# SD_Card_and_Debug_Uart.net
KiCad netlist of a schematic drawn in Altium Designer
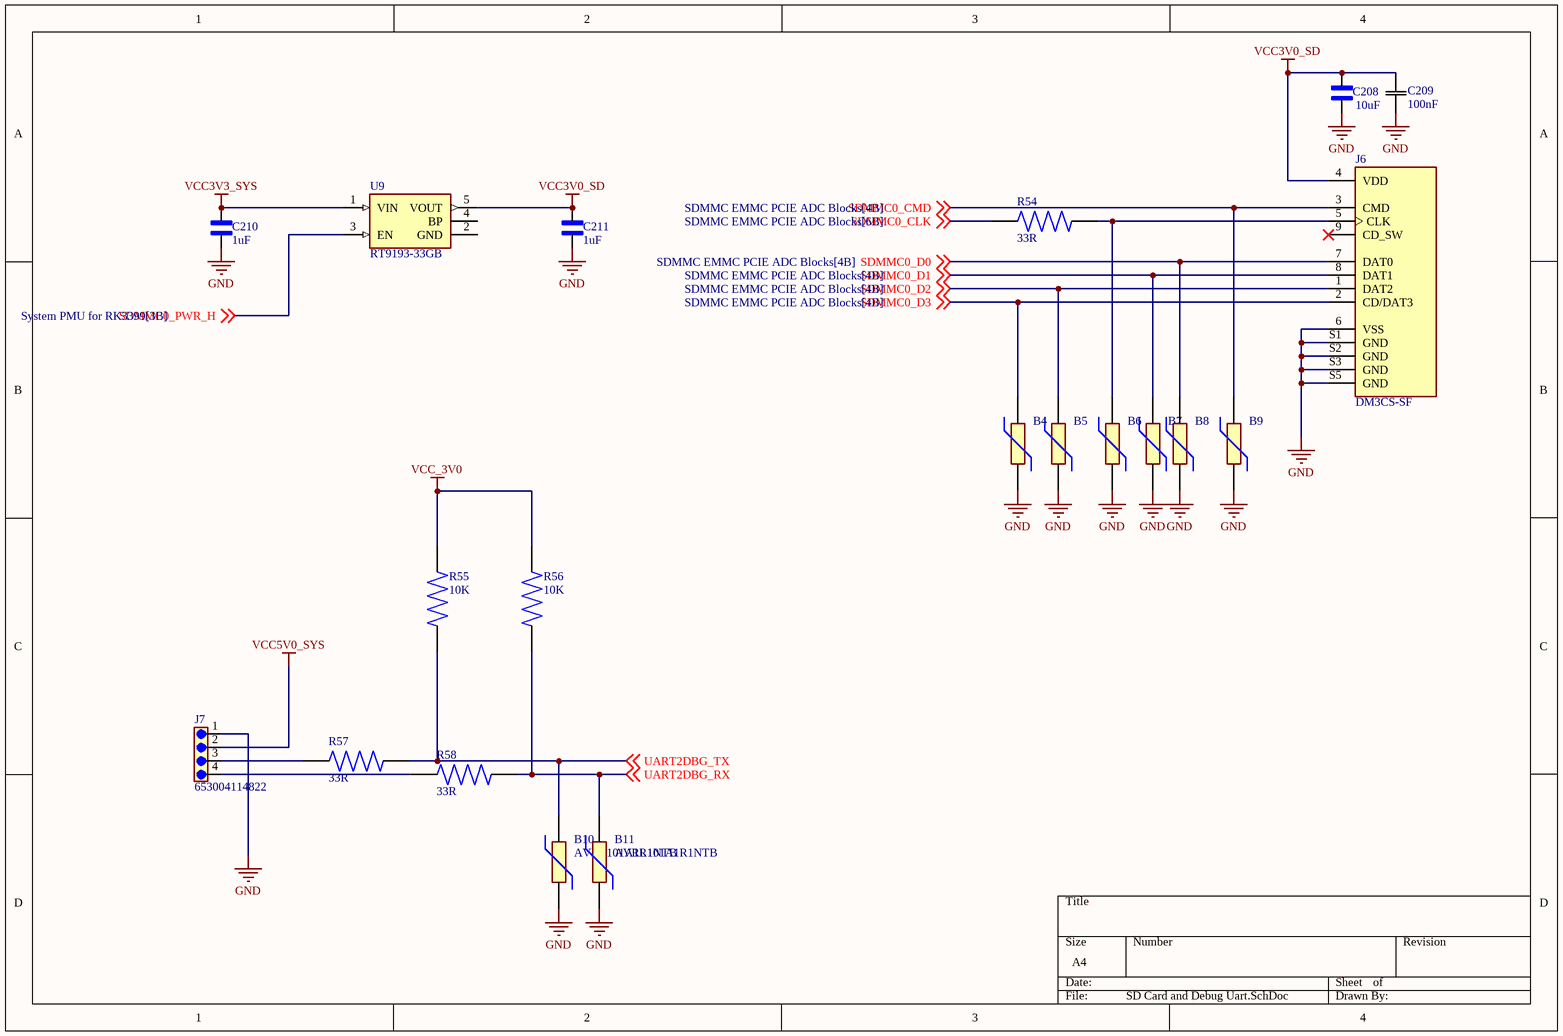
[diagram p0: SD Card and Debug Uart.SchDoc]

(export (version "E")
  (design (tool "Eeschema 10.0.6"))
  (components
    (comp (ref "B4")
      (value "~")
      (footprint "VARC1005X55N")
      (fields
        (field (name "MANUFACTURER_PART_NUMBER") "AVRL101A1R1NTB")
        (field (name "MOUSER PART NUMBER") "810-AVRL101A1R1NTB")
      )
      (libsource (lib "AVRL101A1R1NTB") (part "AVRL101A1R1NTB"))
    )
    (comp (ref "B5")
      (value "~")
      (footprint "VARC1005X55N")
      (fields
        (field (name "MANUFACTURER_PART_NUMBER") "AVRL101A1R1NTB")
        (field (name "MOUSER PART NUMBER") "810-AVRL101A1R1NTB")
      )
      (libsource (lib "AVRL101A1R1NTB") (part "AVRL101A1R1NTB"))
    )
    (comp (ref "B6")
      (value "~")
      (footprint "VARC1005X55N")
      (fields
        (field (name "MANUFACTURER_PART_NUMBER") "AVRL101A1R1NTB")
        (field (name "MOUSER PART NUMBER") "810-AVRL101A1R1NTB")
      )
      (libsource (lib "AVRL101A1R1NTB") (part "AVRL101A1R1NTB"))
    )
    (comp (ref "B7")
      (value "~")
      (footprint "VARC1005X55N")
      (fields
        (field (name "MANUFACTURER_PART_NUMBER") "AVRL101A1R1NTB")
        (field (name "MOUSER PART NUMBER") "810-AVRL101A1R1NTB")
      )
      (libsource (lib "AVRL101A1R1NTB") (part "AVRL101A1R1NTB"))
    )
    (comp (ref "B8")
      (value "~")
      (footprint "VARC1005X55N")
      (fields
        (field (name "MANUFACTURER_PART_NUMBER") "AVRL101A1R1NTB")
        (field (name "MOUSER PART NUMBER") "810-AVRL101A1R1NTB")
      )
      (libsource (lib "AVRL101A1R1NTB") (part "AVRL101A1R1NTB"))
    )
    (comp (ref "B9")
      (value "~")
      (footprint "VARC1005X55N")
      (fields
        (field (name "MANUFACTURER_PART_NUMBER") "AVRL101A1R1NTB")
        (field (name "MOUSER PART NUMBER") "810-AVRL101A1R1NTB")
      )
      (libsource (lib "AVRL101A1R1NTB") (part "AVRL101A1R1NTB"))
    )
    (comp (ref "B10")
      (value "AVRL101A1R1NTB")
      (footprint "VARC1005X55N")
      (fields (field (name "MOUSER PART NUMBER") "810-AVRL101A1R1NTB"))
      (libsource (lib "AVRL101A1R1NTB") (part "AVRL101A1R1NTB"))
    )
    (comp (ref "B11")
      (value "AVRL101A1R1NTB")
      (footprint "VARC1005X55N")
      (fields (field (name "MOUSER PART NUMBER") "810-AVRL101A1R1NTB"))
      (libsource (lib "AVRL101A1R1NTB") (part "AVRL101A1R1NTB"))
    )
    (comp (ref "C208")
      (value "10uF")
      (footprint "CAPC1005X70N")
      (description "10 ÂµF Â±20% 6.3V Ceramic Capacitor X5R 0402 (1005 Metric)")
      (fields (field (name "MF") "Samsung") (field (name "MP") "CL05A106MQ5NUNC"))
      (libsource (lib "CL05A106MQ5NUNC") (part "CL05A106MQ5NUNC"))
    )
    (comp (ref "C209")
      (value "100nF")
      (footprint "CAP_1005_TDK")
      (description "Description")
      (fields
        (field (name "MANUFACTURER_PART_NUMBER") "C1005X7R1H104M050BB")
        (field (name "COPYRIGHT") "Copyright (C) 2025 Ultra Librarian. All rights reserved.")
      )
      (libsource (lib "C1005X7R1H104M050BB") (part "C1005X7R1H104M050BB"))
    )
    (comp (ref "C210")
      (value "1uF")
      (footprint "CAPC1005X56N")
      (description "1 ÂµF Â±10% 10V Ceramic Capacitor X5R 0402 (1005 Metric)")
      (fields (field (name "MF") "AVX") (field (name "MP") "0402ZD105KAT4A"))
      (libsource (lib "0402ZD105KAT4A") (part "0402ZD105KAT4A"))
    )
    (comp (ref "C211")
      (value "1uF")
      (footprint "CAPC1005X56N")
      (description "1 ÂµF Â±10% 10V Ceramic Capacitor X5R 0402 (1005 Metric)")
      (fields (field (name "MF") "AVX") (field (name "MP") "0402ZD105KAT4A"))
      (libsource (lib "0402ZD105KAT4A") (part "0402ZD105KAT4A"))
    )
    (comp (ref "J6")
      (value "DM3CS-SF")
      (footprint "HRS_DM3CS-SF")
      (description "10 (8 + 2) Position Card Connector Secure Digital - microSDâ„¢ Surface Mount, Right Angle Gold")
      (fields (field (name "MF") "Hirose Electric Co Ltd"))
      (libsource (lib "DM3CS-SF") (part "DM3CS-SF"))
    )
    (comp (ref "J7")
      (value "653004114822")
      (footprint "653004114822")
      (description "CONN, HEADER, 4POS, 1ROW, 1.25MM ROHS COMPLIANT: YES")
      (fields (field (name "MF") "WÃ¼rth Elektronik"))
      (libsource (lib "653004114822") (part "653004114822"))
    )
    (comp (ref "R54")
      (value "33R")
      (footprint "RES_ERA6AHD330V")
      (fields (field (name "MP") "ERA6AHD330V"))
      (libsource (lib "ERA6AHD330V") (part "ERA6AHD330V"))
    )
    (comp (ref "R55")
      (value "10K")
      (footprint "RES_ERA3ARB103V")
      (fields (field (name "MP") "ERA3ARB103V"))
      (libsource (lib "ERA3ARB103V") (part "ERA3ARB103V"))
    )
    (comp (ref "R56")
      (value "10K")
      (footprint "RES_ERA3ARB103V")
      (fields (field (name "MP") "ERA3ARB103V"))
      (libsource (lib "ERA3ARB103V") (part "ERA3ARB103V"))
    )
    (comp (ref "R57")
      (value "33R")
      (footprint "RES_ERA6AHD330V")
      (fields (field (name "MP") "ERA6AHD330V"))
      (libsource (lib "ERA6AHD330V") (part "ERA6AHD330V"))
    )
    (comp (ref "R58")
      (value "33R")
      (footprint "RES_ERA6AHD330V")
      (fields (field (name "MP") "ERA6AHD330V"))
      (libsource (lib "ERA6AHD330V") (part "ERA6AHD330V"))
    )
    (comp (ref "U9")
      (value "RT9193-33GB")
      (footprint "SOT94P279X129-5N")
      (description "Linear Voltage Regulator IC Positive Fixed 1 Output 300mA TSOT-23-5")
      (fields (field (name "MF") "Richtek USA") (field (name "DIGI-KEY_PART_NUMBER") "1028-1014-2-ND"))
      (libsource (lib "RT9193-33GB") (part "RT9193-33GB"))
    )
  )
  (nets
    (net (code "1") (name "GND") (class "Default")
      (node (ref "B10") (pin "1") (pinfunction "1_1") (pintype "passive"))
      (node (ref "B11") (pin "1") (pinfunction "1_1") (pintype "passive"))
      (node (ref "B4") (pin "1") (pinfunction "1_1") (pintype "passive"))
      (node (ref "B5") (pin "1") (pinfunction "1_1") (pintype "passive"))
      (node (ref "B6") (pin "1") (pinfunction "1_1") (pintype "passive"))
      (node (ref "B7") (pin "1") (pinfunction "1_1") (pintype "passive"))
      (node (ref "B8") (pin "1") (pinfunction "1_1") (pintype "passive"))
      (node (ref "B9") (pin "1") (pinfunction "1_1") (pintype "passive"))
      (node (ref "C208") (pin "1") (pinfunction "1_1") (pintype "passive"))
      (node (ref "C209") (pin "1") (pinfunction "1_1") (pintype "passive"))
      (node (ref "C210") (pin "1") (pinfunction "1_1") (pintype "passive"))
      (node (ref "C211") (pin "1") (pinfunction "1_1") (pintype "passive"))
      (node (ref "J6") (pin "6") (pinfunction "VSS_6") (pintype "passive"))
      (node (ref "J6") (pin "S1") (pinfunction "GND_S1") (pintype "passive"))
      (node (ref "J6") (pin "S2") (pinfunction "GND_S2") (pintype "passive"))
      (node (ref "J6") (pin "S3") (pinfunction "GND_S3") (pintype "passive"))
      (node (ref "J6") (pin "S5") (pinfunction "GND_S5") (pintype "passive"))
      (node (ref "J7") (pin "1") (pinfunction "1_1") (pintype "passive"))
    )
    (net (code "2") (name "Net-(J6-CLK)") (class "Default")
      (node (ref "B6") (pin "2") (pinfunction "2_2") (pintype "passive"))
      (node (ref "J6") (pin "5") (pinfunction "CLK_5") (pintype "passive"))
      (node (ref "R54") (pin "2") (pinfunction "2_2") (pintype "passive"))
    )
    (net (code "3") (name "Net-(J7-Pad3)") (class "Default")
      (node (ref "J7") (pin "3") (pinfunction "3_3") (pintype "passive"))
      (node (ref "R57") (pin "1") (pinfunction "1_1") (pintype "passive"))
    )
    (net (code "4") (name "Net-(J7-Pad4)") (class "Default")
      (node (ref "J7") (pin "4") (pinfunction "4_4") (pintype "passive"))
      (node (ref "R58") (pin "1") (pinfunction "1_1") (pintype "passive"))
    )
    (net (code "5") (name "SDMMC0_CLK") (class "Default")
      (node (ref "R54") (pin "1") (pinfunction "1_1") (pintype "passive"))
    )
    (net (code "6") (name "SDMMC0_CMD") (class "Default")
      (node (ref "B9") (pin "2") (pinfunction "2_2") (pintype "passive"))
      (node (ref "J6") (pin "3") (pinfunction "CMD_3") (pintype "passive"))
    )
    (net (code "7") (name "SDMMC0_D0") (class "Default")
      (node (ref "B8") (pin "2") (pinfunction "2_2") (pintype "passive"))
      (node (ref "J6") (pin "7") (pinfunction "DAT0_7") (pintype "passive"))
    )
    (net (code "8") (name "SDMMC0_D1") (class "Default")
      (node (ref "B7") (pin "2") (pinfunction "2_2") (pintype "passive"))
      (node (ref "J6") (pin "8") (pinfunction "DAT1_8") (pintype "passive"))
    )
    (net (code "9") (name "SDMMC0_D2") (class "Default")
      (node (ref "B5") (pin "2") (pinfunction "2_2") (pintype "passive"))
      (node (ref "J6") (pin "1") (pinfunction "DAT2_1") (pintype "passive"))
    )
    (net (code "10") (name "SDMMC0_D3") (class "Default")
      (node (ref "B4") (pin "2") (pinfunction "2_2") (pintype "passive"))
      (node (ref "J6") (pin "2") (pinfunction "CD/DAT3_2") (pintype "passive"))
    )
    (net (code "11") (name "SDMMC0_PWR_H") (class "Default")
      (node (ref "U9") (pin "3") (pinfunction "EN_3") (pintype "input"))
    )
    (net (code "12") (name "UART2DBG_RX") (class "Default")
      (node (ref "B11") (pin "2") (pinfunction "2_2") (pintype "passive"))
      (node (ref "R56") (pin "1") (pinfunction "1_1") (pintype "passive"))
      (node (ref "R58") (pin "2") (pinfunction "2_2") (pintype "passive"))
    )
    (net (code "13") (name "UART2DBG_TX") (class "Default")
      (node (ref "B10") (pin "2") (pinfunction "2_2") (pintype "passive"))
      (node (ref "R55") (pin "1") (pinfunction "1_1") (pintype "passive"))
      (node (ref "R57") (pin "2") (pinfunction "2_2") (pintype "passive"))
    )
    (net (code "14") (name "VCC3V0_SD") (class "Default")
      (node (ref "C208") (pin "2") (pinfunction "2_2") (pintype "passive"))
      (node (ref "C209") (pin "2") (pinfunction "2_2") (pintype "passive"))
      (node (ref "C211") (pin "2") (pinfunction "2_2") (pintype "passive"))
      (node (ref "J6") (pin "4") (pinfunction "VDD_4") (pintype "passive"))
      (node (ref "U9") (pin "5") (pinfunction "VOUT_5") (pintype "output"))
    )
    (net (code "15") (name "VCC3V3_SYS") (class "Default")
      (node (ref "C210") (pin "2") (pinfunction "2_2") (pintype "passive"))
      (node (ref "U9") (pin "1") (pinfunction "VIN_1") (pintype "input"))
    )
    (net (code "16") (name "VCC5V0_SYS") (class "Default")
      (node (ref "J7") (pin "2") (pinfunction "2_2") (pintype "passive"))
    )
    (net (code "17") (name "VCC_3V0") (class "Default")
      (node (ref "R55") (pin "2") (pinfunction "2_2") (pintype "passive"))
      (node (ref "R56") (pin "2") (pinfunction "2_2") (pintype "passive"))
    )
    (net (code "18") (name "unconnected-(J6-CD_SW-Pad9)") (class "Default")
      (node (ref "J6") (pin "9") (pinfunction "CD_SW_9") (pintype "passive+no_connect"))
    )
    (net (code "19") (name "unconnected-(U9-BP-Pad4)") (class "Default")
      (node (ref "U9") (pin "4") (pinfunction "BP_4") (pintype "passive"))
    )
    (net (code "20") (name "unconnected-(U9-GND-Pad2)") (class "Default")
      (node (ref "U9") (pin "2") (pinfunction "GND_2") (pintype "power_in"))
    )
  )
)
